# DIO_MCX_Isolated.net
KiCad netlist of a schematic drawn in Altium Designer
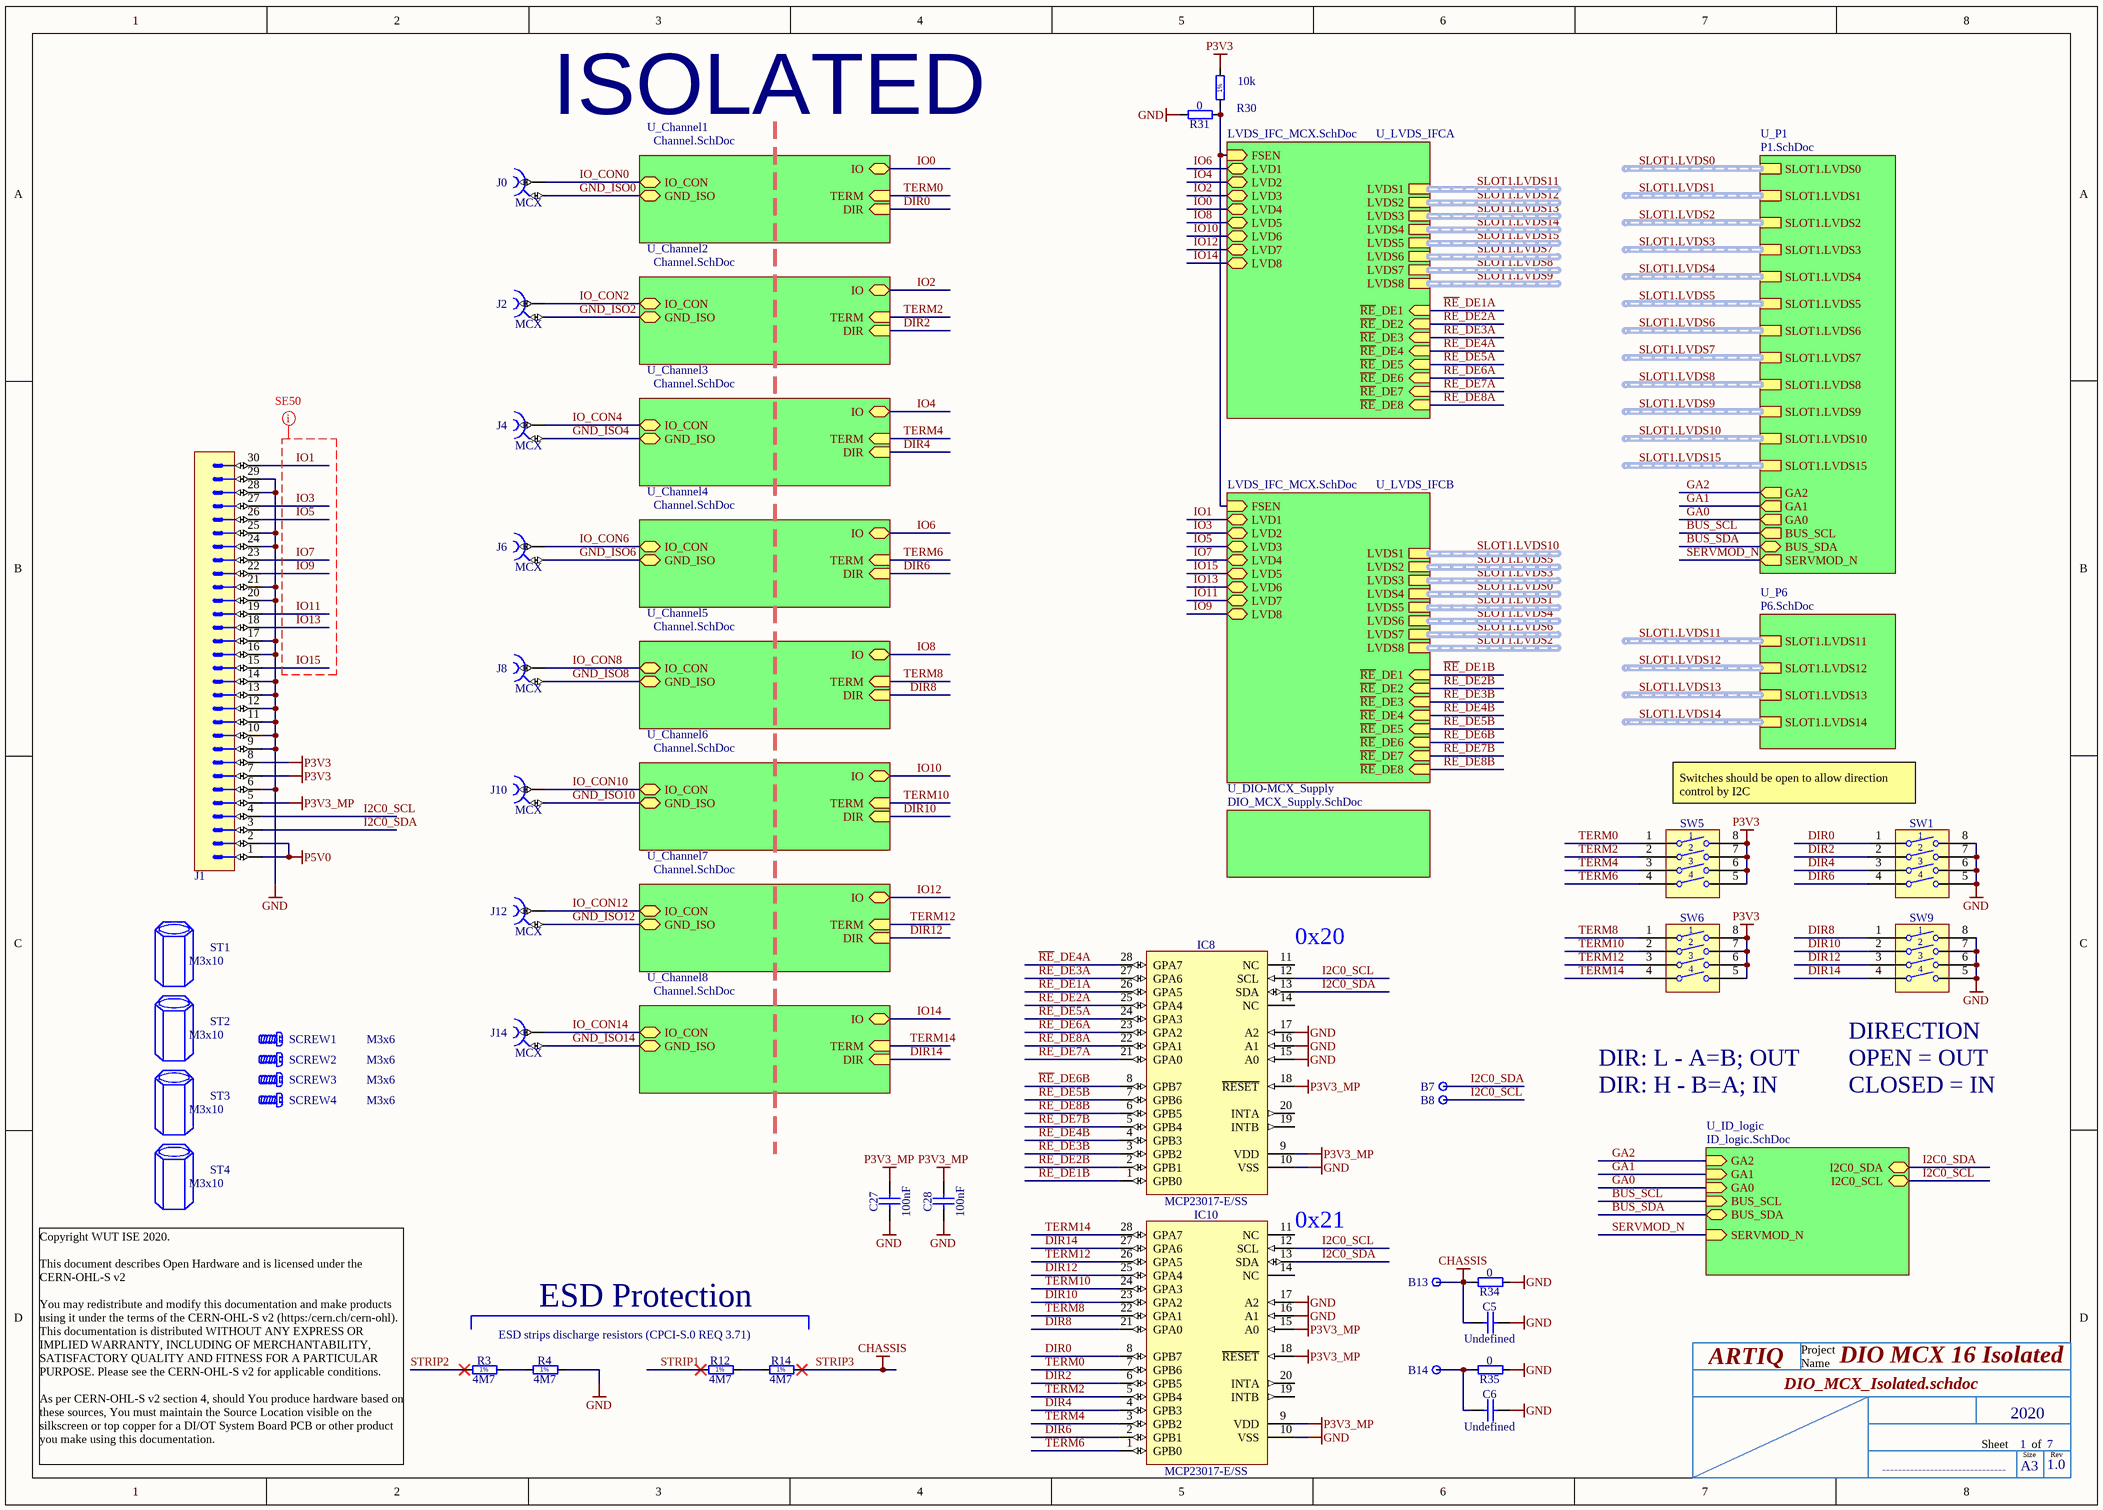
[diagram p0: DIO_MCX_Isolated.schdoc]

(export (version "E")
  (design (tool "Eeschema 10.0.6"))
  (components
    (comp (ref "B7")
      (value "Plated Hole")
      (footprint "c130h60")
      (description "Single Terminal Socket")
      (fields (field (name "PART NUMBER") "PLATED_HOLE0.6_PAD1.3") (field (name "AUTHOR") "CERN DEM MR"))
      (libsource (lib "Eletro-mechanical") (part "Single Terminal Socket"))
    )
    (comp (ref "B8")
      (value "Plated Hole")
      (footprint "c130h60")
      (description "Single Terminal Socket")
      (fields (field (name "PART NUMBER") "PLATED_HOLE0.6_PAD1.3") (field (name "AUTHOR") "CERN DEM MR"))
      (libsource (lib "Eletro-mechanical") (part "Single Terminal Socket"))
    )
    (comp (ref "B13")
      (value "Plated Hole")
      (footprint "MTG270_500")
      (description "Single Terminal Socket")
      (fields (field (name "PART NUMBER") "PLATED_HOLE2.7_PAD5.0") (field (name "AUTHOR") "CERN DEM JMW"))
      (libsource (lib "Eletro-mechanical") (part "Single Terminal Socket"))
    )
    (comp (ref "B14")
      (value "Plated Hole")
      (footprint "MTG270_500")
      (description "Single Terminal Socket")
      (fields (field (name "PART NUMBER") "PLATED_HOLE2.7_PAD5.0") (field (name "AUTHOR") "CERN DEM JMW"))
      (libsource (lib "Eletro-mechanical") (part "Single Terminal Socket"))
    )
    (comp (ref "C5")
      (value "Undefined")
      (footprint "CAPC2012X135N")
      (description "Non-polarised capacitor")
      (fields (field (name "PART NUMBER") "CC0805_NO-VALUE") (field (name "AUTHOR") "CERN DEM JLC"))
      (libsource (lib "Capacitors") (part "Capacitor - non polarized"))
    )
    (comp (ref "C6")
      (value "Undefined")
      (footprint "CAPC2012X135N")
      (description "Non-polarised capacitor")
      (fields (field (name "PART NUMBER") "CC0805_NO-VALUE") (field (name "AUTHOR") "CERN DEM JLC"))
      (libsource (lib "Capacitors") (part "Capacitor - non polarized"))
    )
    (comp (ref "C27")
      (value "100nF")
      (footprint "CAPC1005X55N")
      (description "Non-polarised capacitor")
      (fields
        (field (name "PART NUMBER") "CC0402_100NF_50V_10%_X7R")
        (field (name "VOLTAGE") "50V")
        (field (name "AUTHOR") "CERN DEM MR")
      )
      (libsource (lib "Capacitors") (part "Capacitor - non polarized"))
    )
    (comp (ref "C28")
      (value "100nF")
      (footprint "CAPC1005X55N")
      (description "Non-polarised capacitor")
      (fields
        (field (name "PART NUMBER") "CC0402_100NF_50V_10%_X7R")
        (field (name "VOLTAGE") "50V")
        (field (name "AUTHOR") "CERN DEM MR")
      )
      (libsource (lib "Capacitors") (part "Capacitor - non polarized"))
    )
    (comp (ref "IC8")
      (value "MCP23017-E/SS")
      (footprint "SOP65P780X200-28N")
      (description "16-bit I/O Port Expander With Serial Interface")
      (fields (field (name "MANUFACTURER") "MICROCHIP TECHNOLOGY") (field (name "AUTHOR") "CERN DEM JLC"))
      (libsource (lib "ICs And Semiconductors") (part "MCP23017-E/SS"))
    )
    (comp (ref "IC10")
      (value "MCP23017-E/SS")
      (footprint "SOP65P780X200-28N")
      (description "16-bit I/O Port Expander With Serial Interface")
      (fields (field (name "MANUFACTURER") "MICROCHIP TECHNOLOGY") (field (name "AUTHOR") "CERN DEM JLC"))
      (libsource (lib "ICs And Semiconductors") (part "MCP23017-E/SS"))
    )
    (comp (ref "J0")
      (value "MCX")
      (footprint "BEL_133-3701-801")
      (fields
        (field (name "PART NUMBER") "BELFUSE_133-3701-801")
        (field (name "MANUFACTURER") "BEL")
        (field (name "MANUFACTURER PART NUMBER") "133-3701-801")
        (field (name "AUTHOR") "CERN DEM MR")
      )
      (libsource (lib "Connectors") (part "Coax_1Female_1Shield"))
    )
    (comp (ref "J1")
      (value "~")
      (footprint "3M_N2530-6002RB")
      (description "Connector 30 Male")
      (fields
        (field (name "PART NUMBER") "3M_N2530-6002RB")
        (field (name "MANUFACTURER") "3M")
        (field (name "AUTHOR") "CERN DEM JLC")
      )
      (libsource (lib "Connectors") (part "Connector 30 Male"))
    )
    (comp (ref "J2")
      (value "MCX")
      (footprint "BEL_133-3701-801")
      (fields
        (field (name "PART NUMBER") "BELFUSE_133-3701-801")
        (field (name "MANUFACTURER") "BEL")
        (field (name "MANUFACTURER PART NUMBER") "133-3701-801")
        (field (name "AUTHOR") "CERN DEM MR")
      )
      (libsource (lib "Connectors") (part "Coax_1Female_1Shield"))
    )
    (comp (ref "J4")
      (value "MCX")
      (footprint "BEL_133-3701-801")
      (fields
        (field (name "PART NUMBER") "BELFUSE_133-3701-801")
        (field (name "MANUFACTURER") "BEL")
        (field (name "MANUFACTURER PART NUMBER") "133-3701-801")
        (field (name "AUTHOR") "CERN DEM MR")
      )
      (libsource (lib "Connectors") (part "Coax_1Female_1Shield"))
    )
    (comp (ref "J6")
      (value "MCX")
      (footprint "BEL_133-3701-801")
      (fields
        (field (name "PART NUMBER") "BELFUSE_133-3701-801")
        (field (name "MANUFACTURER") "BEL")
        (field (name "MANUFACTURER PART NUMBER") "133-3701-801")
        (field (name "AUTHOR") "CERN DEM MR")
      )
      (libsource (lib "Connectors") (part "Coax_1Female_1Shield"))
    )
    (comp (ref "J8")
      (value "MCX")
      (footprint "BEL_133-3701-801")
      (fields
        (field (name "PART NUMBER") "BELFUSE_133-3701-801")
        (field (name "MANUFACTURER") "BEL")
        (field (name "MANUFACTURER PART NUMBER") "133-3701-801")
        (field (name "AUTHOR") "CERN DEM MR")
      )
      (libsource (lib "Connectors") (part "Coax_1Female_1Shield"))
    )
    (comp (ref "J10")
      (value "MCX")
      (footprint "BEL_133-3701-801")
      (fields
        (field (name "PART NUMBER") "BELFUSE_133-3701-801")
        (field (name "MANUFACTURER") "BEL")
        (field (name "MANUFACTURER PART NUMBER") "133-3701-801")
        (field (name "AUTHOR") "CERN DEM MR")
      )
      (libsource (lib "Connectors") (part "Coax_1Female_1Shield"))
    )
    (comp (ref "J12")
      (value "MCX")
      (footprint "BEL_133-3701-801")
      (fields
        (field (name "PART NUMBER") "BELFUSE_133-3701-801")
        (field (name "MANUFACTURER") "BEL")
        (field (name "MANUFACTURER PART NUMBER") "133-3701-801")
        (field (name "AUTHOR") "CERN DEM MR")
      )
      (libsource (lib "Connectors") (part "Coax_1Female_1Shield"))
    )
    (comp (ref "J14")
      (value "MCX")
      (footprint "BEL_133-3701-801")
      (fields
        (field (name "PART NUMBER") "BELFUSE_133-3701-801")
        (field (name "MANUFACTURER") "BEL")
        (field (name "MANUFACTURER PART NUMBER") "133-3701-801")
        (field (name "AUTHOR") "CERN DEM MR")
      )
      (libsource (lib "Connectors") (part "Coax_1Female_1Shield"))
    )
    (comp (ref "R3")
      (value "4M7")
      (footprint "RESC2113X55N")
      (description "Resistor - 1%")
      (fields
        (field (name "PART NUMBER") "R0805_4M7_1%_0.125W_100PPM_VISHAY_CRCW e3")
        (field (name "POWER") "0.125W")
        (field (name "AUTHOR") "CERN DEM BR")
      )
      (libsource (lib "Resistors") (part "Resistor - 1%"))
    )
    (comp (ref "R4")
      (value "4M7")
      (footprint "RESC2113X55N")
      (description "Resistor - 1%")
      (fields
        (field (name "PART NUMBER") "R0805_4M7_1%_0.125W_100PPM_VISHAY_CRCW e3")
        (field (name "POWER") "0.125W")
        (field (name "AUTHOR") "CERN DEM BR")
      )
      (libsource (lib "Resistors") (part "Resistor - 1%"))
    )
    (comp (ref "R12")
      (value "4M7")
      (footprint "RESC2113X55N")
      (description "Resistor - 1%")
      (fields
        (field (name "PART NUMBER") "R0805_4M7_1%_0.125W_100PPM_VISHAY_CRCW e3")
        (field (name "POWER") "0.125W")
        (field (name "AUTHOR") "CERN DEM BR")
      )
      (libsource (lib "Resistors") (part "Resistor - 1%"))
    )
    (comp (ref "R14")
      (value "4M7")
      (footprint "RESC2113X55N")
      (description "Resistor - 1%")
      (fields
        (field (name "PART NUMBER") "R0805_4M7_1%_0.125W_100PPM_VISHAY_CRCW e3")
        (field (name "POWER") "0.125W")
        (field (name "AUTHOR") "CERN DEM BR")
      )
      (libsource (lib "Resistors") (part "Resistor - 1%"))
    )
    (comp (ref "R30")
      (value "10k")
      (footprint "RESC1005X40N")
      (description "Resistor - 1%")
      (fields
        (field (name "PART NUMBER") "R0402_10K_1%_0.0625W_100PPM")
        (field (name "POWER") "0.0625W")
        (field (name "AUTHOR") "CERN DEM JLC")
      )
      (libsource (lib "Resistors") (part "Resistor - 1%"))
    )
    (comp (ref "R31")
      (value "0")
      (footprint "RESC1608X55N")
      (description "Resistor")
      (fields
        (field (name "PART NUMBER") "R0603_0R_JUMPER")
        (field (name "MANUFACTURER") "GENERIC")
        (field (name "AUTHOR") "CERN DEM JLC")
      )
      (libsource (lib "Resistors") (part "Resistor"))
    )
    (comp (ref "R34")
      (value "0")
      (footprint "RESC1608X55N")
      (description "Resistor")
      (fields
        (field (name "PART NUMBER") "R0603_0R_JUMPER")
        (field (name "MANUFACTURER") "GENERIC")
        (field (name "AUTHOR") "CERN DEM JLC")
      )
      (libsource (lib "Resistors") (part "Resistor"))
    )
    (comp (ref "R35")
      (value "0")
      (footprint "RESC1608X55N")
      (description "Resistor")
      (fields
        (field (name "PART NUMBER") "R0603_0R_JUMPER")
        (field (name "MANUFACTURER") "GENERIC")
        (field (name "AUTHOR") "CERN DEM JLC")
      )
      (libsource (lib "Resistors") (part "Resistor"))
    )
    (comp (ref "SCREW1")
      (value "M3x6")
      (footprint "BOSSARD_BN5687-3061605_v")
      (description "Screw")
      (fields
        (field (name "PART NUMBER") "BOSSARD_BN5687-3061605_v")
        (field (name "MANUFACTURER") "BOSSARD")
        (field (name "AUTHOR") "CERN DEM JLC")
      )
      (libsource (lib "Eletro-mechanical") (part "Screw"))
    )
    (comp (ref "SCREW2")
      (value "M3x6")
      (footprint "BOSSARD_BN5687-3061605_v")
      (description "Screw")
      (fields
        (field (name "PART NUMBER") "BOSSARD_BN5687-3061605_v")
        (field (name "MANUFACTURER") "BOSSARD")
        (field (name "AUTHOR") "CERN DEM JLC")
      )
      (libsource (lib "Eletro-mechanical") (part "Screw"))
    )
    (comp (ref "SCREW3")
      (value "M3x6")
      (footprint "BOSSARD_BN5687-3061605_v")
      (description "Screw")
      (fields
        (field (name "PART NUMBER") "BOSSARD_BN5687-3061605_v")
        (field (name "MANUFACTURER") "BOSSARD")
        (field (name "AUTHOR") "CERN DEM JLC")
      )
      (libsource (lib "Eletro-mechanical") (part "Screw"))
    )
    (comp (ref "SCREW4")
      (value "M3x6")
      (footprint "BOSSARD_BN5687-3061605_v")
      (description "Screw")
      (fields
        (field (name "PART NUMBER") "BOSSARD_BN5687-3061605_v")
        (field (name "MANUFACTURER") "BOSSARD")
        (field (name "AUTHOR") "CERN DEM JLC")
      )
      (libsource (lib "Eletro-mechanical") (part "Screw"))
    )
    (comp (ref "ST1")
      (value "M3x10")
      (footprint "HARWIN_R25-1001002")
      (description "M3x10 standoff")
      (fields
        (field (name "PART NUMBER") "DREMEC_TFF-M3X10/DR124")
        (field (name "MANUFACTURER") "DREMEC")
        (field (name "AUTHOR") "GK")
      )
      (libsource (lib "Mechanical") (part "MECH_Standoff_M3x10"))
    )
    (comp (ref "ST2")
      (value "M3x10")
      (footprint "HARWIN_R25-1001002")
      (description "M3x10 standoff")
      (fields
        (field (name "PART NUMBER") "DREMEC_TFF-M3X10/DR124")
        (field (name "MANUFACTURER") "DREMEC")
        (field (name "AUTHOR") "GK")
      )
      (libsource (lib "Mechanical") (part "MECH_Standoff_M3x10"))
    )
    (comp (ref "ST3")
      (value "M3x10")
      (footprint "HARWIN_R25-1001002")
      (description "M3x10 standoff")
      (fields
        (field (name "PART NUMBER") "DREMEC_TFF-M3X10/DR124")
        (field (name "MANUFACTURER") "DREMEC")
        (field (name "AUTHOR") "GK")
      )
      (libsource (lib "Mechanical") (part "MECH_Standoff_M3x10"))
    )
    (comp (ref "ST4")
      (value "M3x10")
      (footprint "HARWIN_R25-1001002")
      (description "M3x10 standoff")
      (fields
        (field (name "PART NUMBER") "DREMEC_TFF-M3X10/DR124")
        (field (name "MANUFACTURER") "DREMEC")
        (field (name "AUTHOR") "GK")
      )
      (libsource (lib "Mechanical") (part "MECH_Standoff_M3x10"))
    )
    (comp (ref "SW1")
      (value "Switch")
      (footprint "SW_OMRON_A6S-4102-H")
      (description "4 Ways SPST DIP Switch")
      (fields
        (field (name "PART NUMBER") "SW_OMRON_A6S-4102-H")
        (field (name "MANUFACTURER") "OMRON")
        (field (name "AUTHOR") "CERN DEM JMW")
      )
      (libsource (lib "Eletro-mechanical") (part "SW 4x SPST DIP Switch"))
    )
    (comp (ref "SW5")
      (value "Switch")
      (footprint "SW_OMRON_A6S-4102-H")
      (description "4 Ways SPST DIP Switch")
      (fields
        (field (name "PART NUMBER") "SW_OMRON_A6S-4102-H")
        (field (name "MANUFACTURER") "OMRON")
        (field (name "AUTHOR") "CERN DEM JMW")
      )
      (libsource (lib "Eletro-mechanical") (part "SW 4x SPST DIP Switch"))
    )
    (comp (ref "SW6")
      (value "Switch")
      (footprint "SW_OMRON_A6S-4102-H")
      (description "4 Ways SPST DIP Switch")
      (fields
        (field (name "PART NUMBER") "SW_OMRON_A6S-4102-H")
        (field (name "MANUFACTURER") "OMRON")
        (field (name "AUTHOR") "CERN DEM JMW")
      )
      (libsource (lib "Eletro-mechanical") (part "SW 4x SPST DIP Switch"))
    )
    (comp (ref "SW9")
      (value "Switch")
      (footprint "SW_OMRON_A6S-4102-H")
      (description "4 Ways SPST DIP Switch")
      (fields
        (field (name "PART NUMBER") "SW_OMRON_A6S-4102-H")
        (field (name "MANUFACTURER") "OMRON")
        (field (name "AUTHOR") "CERN DEM JMW")
      )
      (libsource (lib "Eletro-mechanical") (part "SW 4x SPST DIP Switch"))
    )
  )
  (nets
    (net (code "19") (name "/DIR0") (class "Default")
      (node (ref "IC10") (pin "8") (pinfunction "GPB7_8") (pintype "bidirectional"))
      (node (ref "SW1") (pin "1") (pinfunction "1_1") (pintype "passive"))
    )
    (net (code "20") (name "/DIR2") (class "Default")
      (node (ref "IC10") (pin "6") (pinfunction "GPB5_6") (pintype "bidirectional"))
      (node (ref "SW1") (pin "2") (pinfunction "2_2") (pintype "passive"))
    )
    (net (code "21") (name "/DIR4") (class "Default")
      (node (ref "IC10") (pin "4") (pinfunction "GPB3_4") (pintype "bidirectional"))
      (node (ref "SW1") (pin "3") (pinfunction "3_3") (pintype "passive"))
    )
    (net (code "22") (name "/DIR6") (class "Default")
      (node (ref "IC10") (pin "2") (pinfunction "GPB1_2") (pintype "bidirectional"))
      (node (ref "SW1") (pin "4") (pinfunction "4_4") (pintype "passive"))
    )
    (net (code "23") (name "/DIR8") (class "Default")
      (node (ref "IC10") (pin "21") (pinfunction "GPA0_21") (pintype "bidirectional"))
      (node (ref "SW9") (pin "1") (pinfunction "1_1") (pintype "passive"))
    )
    (net (code "24") (name "/DIR10") (class "Default")
      (node (ref "IC10") (pin "23") (pinfunction "GPA2_23") (pintype "bidirectional"))
      (node (ref "SW9") (pin "2") (pinfunction "2_2") (pintype "passive"))
    )
    (net (code "25") (name "/DIR12") (class "Default")
      (node (ref "IC10") (pin "25") (pinfunction "GPA4_25") (pintype "bidirectional"))
      (node (ref "SW9") (pin "3") (pinfunction "3_3") (pintype "passive"))
    )
    (net (code "26") (name "/DIR14") (class "Default")
      (node (ref "IC10") (pin "27") (pinfunction "GPA6_27") (pintype "bidirectional"))
      (node (ref "SW9") (pin "4") (pinfunction "4_4") (pintype "passive"))
    )
    (net (code "27") (name "/FSEN") (class "Default")
      (node (ref "R30") (pin "1") (pinfunction "1_1") (pintype "passive"))
      (node (ref "R31") (pin "1") (pinfunction "1_1") (pintype "passive"))
    )
    (net (code "31") (name "/GND_ISO0") (class "Default")
      (node (ref "J0") (pin "2") (pinfunction "2_2") (pintype "bidirectional"))
    )
    (net (code "32") (name "/GND_ISO2") (class "Default")
      (node (ref "J2") (pin "2") (pinfunction "2_2") (pintype "bidirectional"))
    )
    (net (code "33") (name "/GND_ISO4") (class "Default")
      (node (ref "J4") (pin "2") (pinfunction "2_2") (pintype "bidirectional"))
    )
    (net (code "34") (name "/GND_ISO6") (class "Default")
      (node (ref "J6") (pin "2") (pinfunction "2_2") (pintype "bidirectional"))
    )
    (net (code "35") (name "/GND_ISO8") (class "Default")
      (node (ref "J8") (pin "2") (pinfunction "2_2") (pintype "bidirectional"))
    )
    (net (code "36") (name "/GND_ISO10") (class "Default")
      (node (ref "J10") (pin "2") (pinfunction "2_2") (pintype "bidirectional"))
    )
    (net (code "37") (name "/GND_ISO12") (class "Default")
      (node (ref "J12") (pin "2") (pinfunction "2_2") (pintype "bidirectional"))
    )
    (net (code "38") (name "/GND_ISO14") (class "Default")
      (node (ref "J14") (pin "2") (pinfunction "2_2") (pintype "bidirectional"))
    )
    (net (code "39") (name "/I2C0_SCL") (class "Default")
      (node (ref "B8") (pin "1") (pinfunction "1_1") (pintype "bidirectional"))
      (node (ref "IC10") (pin "12") (pinfunction "SCL_12") (pintype "input"))
      (node (ref "IC8") (pin "12") (pinfunction "SCL_12") (pintype "input"))
      (node (ref "J1") (pin "4") (pinfunction "4_4") (pintype "bidirectional"))
    )
    (net (code "40") (name "/I2C0_SDA") (class "Default")
      (node (ref "B7") (pin "1") (pinfunction "1_1") (pintype "bidirectional"))
      (node (ref "IC10") (pin "13") (pinfunction "SDA_13") (pintype "bidirectional"))
      (node (ref "IC8") (pin "13") (pinfunction "SDA_13") (pintype "bidirectional"))
      (node (ref "J1") (pin "3") (pinfunction "3_3") (pintype "bidirectional"))
    )
    (net (code "42") (name "/IO1") (class "Default")
      (node (ref "J1") (pin "30") (pinfunction "30_30") (pintype "bidirectional"))
    )
    (net (code "44") (name "/IO3") (class "Default")
      (node (ref "J1") (pin "27") (pinfunction "27_27") (pintype "bidirectional"))
    )
    (net (code "46") (name "/IO5") (class "Default")
      (node (ref "J1") (pin "26") (pinfunction "26_26") (pintype "bidirectional"))
    )
    (net (code "48") (name "/IO7") (class "Default")
      (node (ref "J1") (pin "23") (pinfunction "23_23") (pintype "bidirectional"))
    )
    (net (code "50") (name "/IO9") (class "Default")
      (node (ref "J1") (pin "22") (pinfunction "22_22") (pintype "bidirectional"))
    )
    (net (code "52") (name "/IO11") (class "Default")
      (node (ref "J1") (pin "19") (pinfunction "19_19") (pintype "bidirectional"))
    )
    (net (code "54") (name "/IO13") (class "Default")
      (node (ref "J1") (pin "18") (pinfunction "18_18") (pintype "bidirectional"))
    )
    (net (code "56") (name "/IO15") (class "Default")
      (node (ref "J1") (pin "15") (pinfunction "15_15") (pintype "bidirectional"))
    )
    (net (code "57") (name "/IO_CON0") (class "Default")
      (node (ref "J0") (pin "1") (pinfunction "1_1") (pintype "bidirectional"))
    )
    (net (code "58") (name "/IO_CON2") (class "Default")
      (node (ref "J2") (pin "1") (pinfunction "1_1") (pintype "bidirectional"))
    )
    (net (code "59") (name "/IO_CON4") (class "Default")
      (node (ref "J4") (pin "1") (pinfunction "1_1") (pintype "bidirectional"))
    )
    (net (code "60") (name "/IO_CON6") (class "Default")
      (node (ref "J6") (pin "1") (pinfunction "1_1") (pintype "bidirectional"))
    )
    (net (code "61") (name "/IO_CON8") (class "Default")
      (node (ref "J8") (pin "1") (pinfunction "1_1") (pintype "bidirectional"))
    )
    (net (code "62") (name "/IO_CON10") (class "Default")
      (node (ref "J10") (pin "1") (pinfunction "1_1") (pintype "bidirectional"))
    )
    (net (code "63") (name "/IO_CON12") (class "Default")
      (node (ref "J12") (pin "1") (pinfunction "1_1") (pintype "bidirectional"))
    )
    (net (code "64") (name "/IO_CON14") (class "Default")
      (node (ref "J14") (pin "1") (pinfunction "1_1") (pintype "bidirectional"))
    )
    (net (code "66") (name "/STRIP1") (class "Default")
      (node (ref "R12") (pin "1") (pinfunction "1_1") (pintype "passive+no_connect"))
    )
    (net (code "67") (name "/STRIP2") (class "Default")
      (node (ref "R3") (pin "1") (pinfunction "1_1") (pintype "passive+no_connect"))
    )
    (net (code "68") (name "/TERM0") (class "Default")
      (node (ref "IC10") (pin "7") (pinfunction "GPB6_7") (pintype "bidirectional"))
      (node (ref "SW5") (pin "1") (pinfunction "1_1") (pintype "passive"))
    )
    (net (code "69") (name "/TERM2") (class "Default")
      (node (ref "IC10") (pin "5") (pinfunction "GPB4_5") (pintype "bidirectional"))
      (node (ref "SW5") (pin "2") (pinfunction "2_2") (pintype "passive"))
    )
    (net (code "70") (name "/TERM4") (class "Default")
      (node (ref "IC10") (pin "3") (pinfunction "GPB2_3") (pintype "bidirectional"))
      (node (ref "SW5") (pin "3") (pinfunction "3_3") (pintype "passive"))
    )
    (net (code "71") (name "/TERM6") (class "Default")
      (node (ref "IC10") (pin "1") (pinfunction "GPB0_1") (pintype "bidirectional"))
      (node (ref "SW5") (pin "4") (pinfunction "4_4") (pintype "passive"))
    )
    (net (code "72") (name "/TERM8") (class "Default")
      (node (ref "IC10") (pin "22") (pinfunction "GPA1_22") (pintype "bidirectional"))
      (node (ref "SW6") (pin "1") (pinfunction "1_1") (pintype "passive"))
    )
    (net (code "73") (name "/TERM10") (class "Default")
      (node (ref "IC10") (pin "24") (pinfunction "GPA3_24") (pintype "bidirectional"))
      (node (ref "SW6") (pin "2") (pinfunction "2_2") (pintype "passive"))
    )
    (net (code "74") (name "/TERM12") (class "Default")
      (node (ref "IC10") (pin "26") (pinfunction "GPA5_26") (pintype "bidirectional"))
      (node (ref "SW6") (pin "3") (pinfunction "3_3") (pintype "passive"))
    )
    (net (code "75") (name "/TERM14") (class "Default")
      (node (ref "IC10") (pin "28") (pinfunction "GPA7_28") (pintype "bidirectional"))
      (node (ref "SW6") (pin "4") (pinfunction "4_4") (pintype "passive"))
    )
    (net (code "92") (name "/~{RE}_DE1A") (class "Default")
      (node (ref "IC8") (pin "26") (pinfunction "GPA5_26") (pintype "bidirectional"))
    )
    (net (code "93") (name "/~{RE}_DE1B") (class "Default")
      (node (ref "IC8") (pin "1") (pinfunction "GPB0_1") (pintype "bidirectional"))
    )
    (net (code "94") (name "/~{RE}_DE2A") (class "Default")
      (node (ref "IC8") (pin "25") (pinfunction "GPA4_25") (pintype "bidirectional"))
    )
    (net (code "95") (name "/~{RE}_DE2B") (class "Default")
      (node (ref "IC8") (pin "2") (pinfunction "GPB1_2") (pintype "bidirectional"))
    )
    (net (code "96") (name "/~{RE}_DE3A") (class "Default")
      (node (ref "IC8") (pin "27") (pinfunction "GPA6_27") (pintype "bidirectional"))
    )
    (net (code "97") (name "/~{RE}_DE3B") (class "Default")
      (node (ref "IC8") (pin "3") (pinfunction "GPB2_3") (pintype "bidirectional"))
    )
    (net (code "98") (name "/~{RE}_DE4A") (class "Default")
      (node (ref "IC8") (pin "28") (pinfunction "GPA7_28") (pintype "bidirectional"))
    )
    (net (code "99") (name "/~{RE}_DE4B") (class "Default")
      (node (ref "IC8") (pin "4") (pinfunction "GPB3_4") (pintype "bidirectional"))
    )
    (net (code "100") (name "/~{RE}_DE5A") (class "Default")
      (node (ref "IC8") (pin "24") (pinfunction "GPA3_24") (pintype "bidirectional"))
    )
    (net (code "101") (name "/~{RE}_DE5B") (class "Default")
      (node (ref "IC8") (pin "7") (pinfunction "GPB6_7") (pintype "bidirectional"))
    )
    (net (code "102") (name "/~{RE}_DE6A") (class "Default")
      (node (ref "IC8") (pin "23") (pinfunction "GPA2_23") (pintype "bidirectional"))
    )
    (net (code "103") (name "/~{RE}_DE6B") (class "Default")
      (node (ref "IC8") (pin "8") (pinfunction "GPB7_8") (pintype "bidirectional"))
    )
    (net (code "104") (name "/~{RE}_DE7A") (class "Default")
      (node (ref "IC8") (pin "21") (pinfunction "GPA0_21") (pintype "bidirectional"))
    )
    (net (code "105") (name "/~{RE}_DE7B") (class "Default")
      (node (ref "IC8") (pin "5") (pinfunction "GPB4_5") (pintype "bidirectional"))
    )
    (net (code "106") (name "/~{RE}_DE8A") (class "Default")
      (node (ref "IC8") (pin "22") (pinfunction "GPA1_22") (pintype "bidirectional"))
    )
    (net (code "107") (name "/~{RE}_DE8B") (class "Default")
      (node (ref "IC8") (pin "6") (pinfunction "GPB5_6") (pintype "bidirectional"))
    )
    (net (code "108") (name "CHASSIS") (class "Default")
      (node (ref "B13") (pin "1") (pinfunction "1_1") (pintype "bidirectional"))
      (node (ref "C5") (pin "1") (pinfunction "1_1") (pintype "passive"))
      (node (ref "R14") (pin "2") (pinfunction "2_2") (pintype "passive"))
      (node (ref "R34") (pin "2") (pinfunction "2_2") (pintype "passive"))
    )
    (net (code "109") (name "GND") (class "Default")
      (node (ref "C27") (pin "1") (pinfunction "1_1") (pintype "passive"))
      (node (ref "C28") (pin "1") (pinfunction "1_1") (pintype "passive"))
      (node (ref "C5") (pin "2") (pinfunction "2_2") (pintype "passive"))
      (node (ref "C6") (pin "2") (pinfunction "2_2") (pintype "passive"))
      (node (ref "IC10") (pin "10") (pinfunction "VSS_10") (pintype "power_in"))
      (node (ref "IC10") (pin "16") (pinfunction "A1_16") (pintype "input"))
      (node (ref "IC10") (pin "17") (pinfunction "A2_17") (pintype "input"))
      (node (ref "IC8") (pin "10") (pinfunction "VSS_10") (pintype "power_in"))
      (node (ref "IC8") (pin "15") (pinfunction "A0_15") (pintype "input"))
      (node (ref "IC8") (pin "16") (pinfunction "A1_16") (pintype "input"))
      (node (ref "IC8") (pin "17") (pinfunction "A2_17") (pintype "input"))
      (node (ref "J1") (pin "10") (pinfunction "10_10") (pintype "bidirectional"))
      (node (ref "J1") (pin "11") (pinfunction "11_11") (pintype "bidirectional"))
      (node (ref "J1") (pin "12") (pinfunction "12_12") (pintype "bidirectional"))
      (node (ref "J1") (pin "13") (pinfunction "13_13") (pintype "bidirectional"))
      (node (ref "J1") (pin "14") (pinfunction "14_14") (pintype "bidirectional"))
      (node (ref "J1") (pin "16") (pinfunction "16_16") (pintype "bidirectional"))
      (node (ref "J1") (pin "17") (pinfunction "17_17") (pintype "bidirectional"))
      (node (ref "J1") (pin "20") (pinfunction "20_20") (pintype "bidirectional"))
      (node (ref "J1") (pin "21") (pinfunction "21_21") (pintype "bidirectional"))
      (node (ref "J1") (pin "24") (pinfunction "24_24") (pintype "bidirectional"))
      (node (ref "J1") (pin "25") (pinfunction "25_25") (pintype "bidirectional"))
      (node (ref "J1") (pin "28") (pinfunction "28_28") (pintype "bidirectional"))
      (node (ref "J1") (pin "29") (pinfunction "29_29") (pintype "bidirectional"))
      (node (ref "J1") (pin "6") (pinfunction "6_6") (pintype "bidirectional"))
      (node (ref "J1") (pin "9") (pinfunction "9_9") (pintype "bidirectional"))
      (node (ref "R31") (pin "2") (pinfunction "2_2") (pintype "passive"))
      (node (ref "R34") (pin "1") (pinfunction "1_1") (pintype "passive"))
      (node (ref "R35") (pin "1") (pinfunction "1_1") (pintype "passive"))
      (node (ref "R4") (pin "2") (pinfunction "2_2") (pintype "passive"))
      (node (ref "SW1") (pin "5") (pinfunction "5_5") (pintype "passive"))
      (node (ref "SW1") (pin "6") (pinfunction "6_6") (pintype "passive"))
      (node (ref "SW1") (pin "7") (pinfunction "7_7") (pintype "passive"))
      (node (ref "SW1") (pin "8") (pinfunction "8_8") (pintype "passive"))
      (node (ref "SW9") (pin "5") (pinfunction "5_5") (pintype "passive"))
      (node (ref "SW9") (pin "6") (pinfunction "6_6") (pintype "passive"))
      (node (ref "SW9") (pin "7") (pinfunction "7_7") (pintype "passive"))
      (node (ref "SW9") (pin "8") (pinfunction "8_8") (pintype "passive"))
    )
    (net (code "110") (name "Net-(B14-Pad1)") (class "Default")
      (node (ref "B14") (pin "1") (pinfunction "1_1") (pintype "bidirectional"))
      (node (ref "C6") (pin "1") (pinfunction "1_1") (pintype "passive"))
      (node (ref "R35") (pin "2") (pinfunction "2_2") (pintype "passive"))
    )
    (net (code "111") (name "Net-(R3-Pad2)") (class "Default")
      (node (ref "R3") (pin "2") (pinfunction "2_2") (pintype "passive"))
      (node (ref "R4") (pin "1") (pinfunction "1_1") (pintype "passive"))
    )
    (net (code "112") (name "Net-(R12-Pad2)") (class "Default")
      (node (ref "R12") (pin "2") (pinfunction "2_2") (pintype "passive"))
      (node (ref "R14") (pin "1") (pinfunction "1_1") (pintype "passive"))
    )
    (net (code "113") (name "P3V3") (class "Default")
      (node (ref "J1") (pin "7") (pinfunction "7_7") (pintype "bidirectional"))
      (node (ref "J1") (pin "8") (pinfunction "8_8") (pintype "bidirectional"))
      (node (ref "R30") (pin "2") (pinfunction "2_2") (pintype "passive"))
      (node (ref "SW5") (pin "5") (pinfunction "5_5") (pintype "passive"))
      (node (ref "SW5") (pin "6") (pinfunction "6_6") (pintype "passive"))
      (node (ref "SW5") (pin "7") (pinfunction "7_7") (pintype "passive"))
      (node (ref "SW5") (pin "8") (pinfunction "8_8") (pintype "passive"))
      (node (ref "SW6") (pin "5") (pinfunction "5_5") (pintype "passive"))
      (node (ref "SW6") (pin "6") (pinfunction "6_6") (pintype "passive"))
      (node (ref "SW6") (pin "7") (pinfunction "7_7") (pintype "passive"))
      (node (ref "SW6") (pin "8") (pinfunction "8_8") (pintype "passive"))
    )
    (net (code "114") (name "P3V3_MP") (class "Default")
      (node (ref "C27") (pin "2") (pinfunction "2_2") (pintype "passive"))
      (node (ref "C28") (pin "2") (pinfunction "2_2") (pintype "passive"))
      (node (ref "IC10") (pin "15") (pinfunction "A0_15") (pintype "input"))
      (node (ref "IC10") (pin "18") (pinfunction "~{RESET}_18") (pintype "input"))
      (node (ref "IC10") (pin "9") (pinfunction "VDD_9") (pintype "power_in"))
      (node (ref "IC8") (pin "18") (pinfunction "~{RESET}_18") (pintype "input"))
      (node (ref "IC8") (pin "9") (pinfunction "VDD_9") (pintype "power_in"))
      (node (ref "J1") (pin "5") (pinfunction "5_5") (pintype "bidirectional"))
    )
    (net (code "115") (name "P5V0") (class "Default")
      (node (ref "J1") (pin "1") (pinfunction "1_1") (pintype "bidirectional"))
      (node (ref "J1") (pin "2") (pinfunction "2_2") (pintype "bidirectional"))
    )
    (net (code "116") (name "unconnected-(IC8-INTA-Pad20)") (class "Default")
      (node (ref "IC8") (pin "20") (pinfunction "INTA_20") (pintype "output"))
    )
    (net (code "117") (name "unconnected-(IC8-INTB-Pad19)") (class "Default")
      (node (ref "IC8") (pin "19") (pinfunction "INTB_19") (pintype "output"))
    )
    (net (code "118") (name "unconnected-(IC8-NC-Pad11)") (class "Default")
      (node (ref "IC8") (pin "11") (pinfunction "NC_11") (pintype "passive"))
    )
    (net (code "119") (name "unconnected-(IC8-NC-Pad14)") (class "Default")
      (node (ref "IC8") (pin "14") (pinfunction "NC_14") (pintype "passive"))
    )
    (net (code "120") (name "unconnected-(IC10-INTA-Pad20)") (class "Default")
      (node (ref "IC10") (pin "20") (pinfunction "INTA_20") (pintype "output"))
    )
    (net (code "121") (name "unconnected-(IC10-INTB-Pad19)") (class "Default")
      (node (ref "IC10") (pin "19") (pinfunction "INTB_19") (pintype "output"))
    )
    (net (code "122") (name "unconnected-(IC10-NC-Pad11)") (class "Default")
      (node (ref "IC10") (pin "11") (pinfunction "NC_11") (pintype "passive"))
    )
    (net (code "123") (name "unconnected-(IC10-NC-Pad14)") (class "Default")
      (node (ref "IC10") (pin "14") (pinfunction "NC_14") (pintype "passive"))
    )
  )
)
